# GamePad.net
KiCad netlist of a schematic drawn in EAGLE
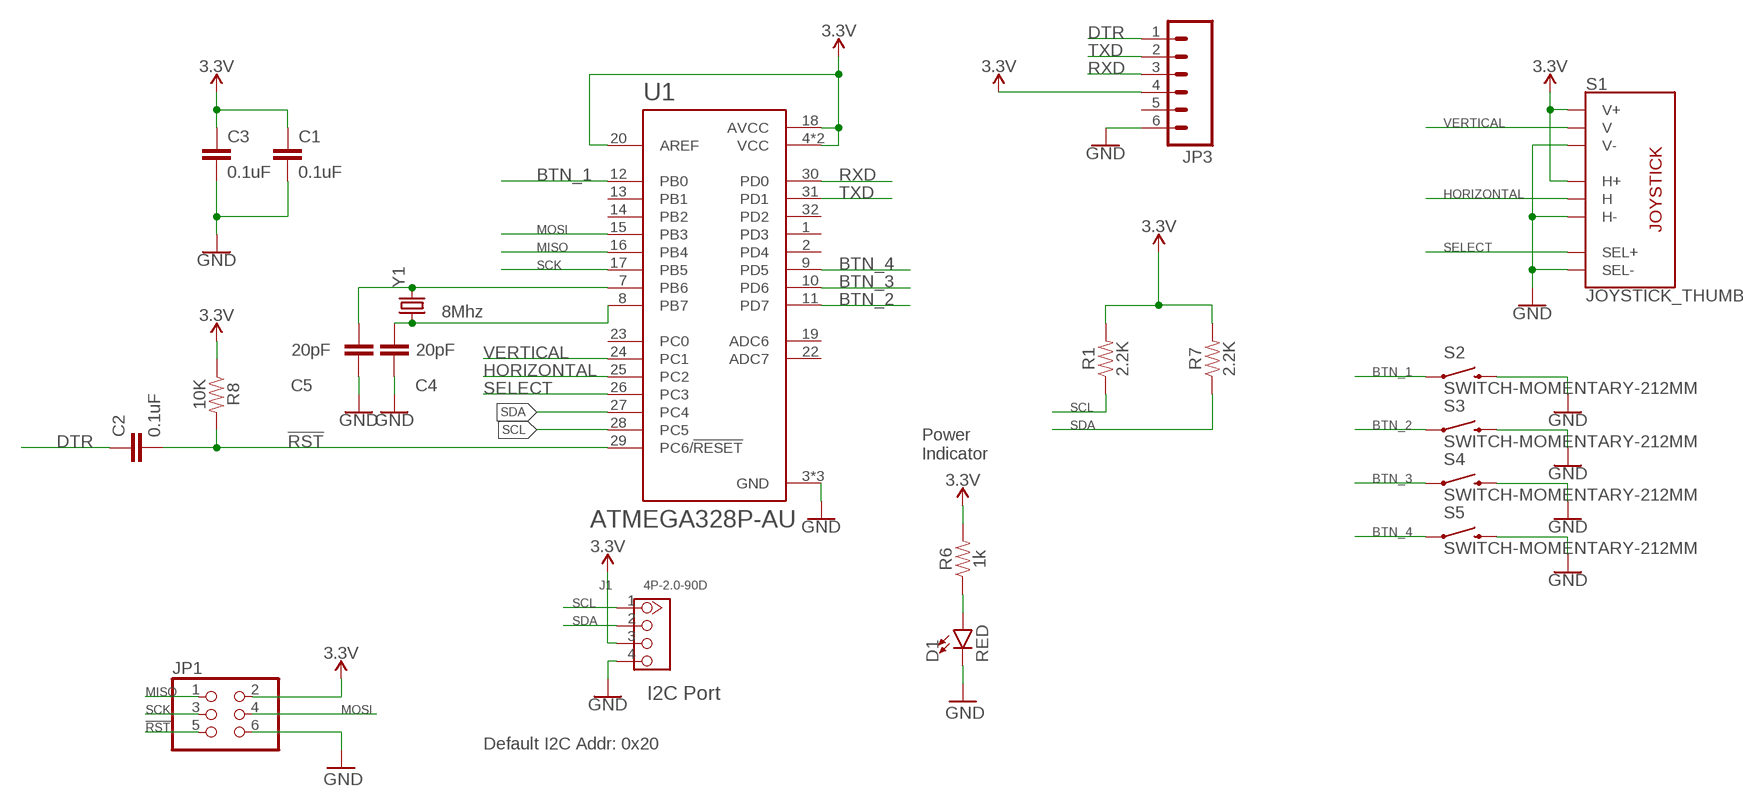
[diagram p0: schematic, sheet 1]

(export (version "E")
  (design (tool "Eeschema 10.0.6"))
  (components
    (comp (ref "C1")
      (value "0.1uF")
      (footprint "eagle-import:0603-CAP")
      (libsource (lib "eagle-import") (part "CAP0603-CAP"))
    )
    (comp (ref "C2")
      (value "0.1uF")
      (footprint "eagle-import:0603-CAP")
      (libsource (lib "eagle-import") (part "CAP0603-CAP"))
    )
    (comp (ref "C3")
      (value "0.1uF")
      (footprint "eagle-import:0603-CAP")
      (libsource (lib "eagle-import") (part "CAP0603-CAP"))
    )
    (comp (ref "C4")
      (value "20pF")
      (footprint "eagle-import:0603-CAP")
      (libsource (lib "eagle-import") (part "CAP0603-CAP"))
    )
    (comp (ref "C5")
      (value "20pF")
      (footprint "eagle-import:0603-CAP")
      (libsource (lib "eagle-import") (part "CAP0603-CAP"))
    )
    (comp (ref "D1")
      (value "RED")
      (footprint "eagle-import:LED-0603")
      (libsource (lib "eagle-import") (part "LED-RED0603"))
    )
    (comp (ref "J1")
      (value "4P-2.0-90D")
      (footprint "eagle-import:HW4-2.0-90D")
      (libsource (lib "eagle-import") (part "GROVE-CONNECTOR-DIP-90D(4P-2.0)"))
    )
    (comp (ref "JP1")
      (value "PINHD-2X3")
      (footprint "eagle-import:2X03")
      (libsource (lib "eagle-import") (part "PINHD-2X3"))
    )
    (comp (ref "JP3")
      (value "M06LOCK")
      (footprint "eagle-import:1X06_LOCK")
      (libsource (lib "eagle-import") (part "M06LOCK"))
    )
    (comp (ref "R1")
      (value "2.2K")
      (footprint "eagle-import:0603")
      (libsource (lib "eagle-import") (part "4.7KOHM-0603-1/10W-1%"))
    )
    (comp (ref "R6")
      (value "1k")
      (footprint "eagle-import:0603")
      (libsource (lib "eagle-import") (part "1KOHM-0603-1/10W-1%"))
    )
    (comp (ref "R7")
      (value "2.2K")
      (footprint "eagle-import:0603")
      (libsource (lib "eagle-import") (part "4.7KOHM-0603-1/10W-1%"))
    )
    (comp (ref "R8")
      (value "10K")
      (footprint "eagle-import:0603")
      (libsource (lib "eagle-import") (part "330OHM-0603-1/10W-1%"))
    )
    (comp (ref "S1")
      (value "JOYSTICK_THUMB")
      (footprint "eagle-import:JOYSTICK")
      (libsource (lib "eagle-import") (part "JOYSTICK_THUMB"))
    )
    (comp (ref "S2")
      (value "SWITCH-MOMENTARY-212MM")
      (footprint "eagle-import:TACTILE-PTH-12MM")
      (libsource (lib "eagle-import") (part "SWITCH-MOMENTARY-212MM"))
    )
    (comp (ref "S3")
      (value "SWITCH-MOMENTARY-212MM")
      (footprint "eagle-import:TACTILE-PTH-12MM")
      (libsource (lib "eagle-import") (part "SWITCH-MOMENTARY-212MM"))
    )
    (comp (ref "S4")
      (value "SWITCH-MOMENTARY-212MM")
      (footprint "eagle-import:TACTILE-PTH-12MM")
      (libsource (lib "eagle-import") (part "SWITCH-MOMENTARY-212MM"))
    )
    (comp (ref "S5")
      (value "SWITCH-MOMENTARY-212MM")
      (footprint "eagle-import:TACTILE-PTH-12MM")
      (libsource (lib "eagle-import") (part "SWITCH-MOMENTARY-212MM"))
    )
    (comp (ref "U1")
      (value "ATMEGA328P-AU")
      (footprint "eagle-import:QFP80P900X900X120-32N")
      (fields (field (name "MF") "Microchip"))
      (libsource (lib "eagle-import") (part "ATMEGA328P-AU"))
    )
    (comp (ref "Y1")
      (value "8Mhz")
      (footprint "eagle-import:HC49UP")
      (libsource (lib "eagle-import") (part "CRYSTALSMD"))
    )
  )
  (nets
    (net (code "1") (name "/BTN_1") (class "Default")
      (node (ref "S2") (pin "1") (pinfunction "1_1") (pintype "passive"))
      (node (ref "U1") (pin "12") (pinfunction "PB0_12") (pintype "bidirectional"))
    )
    (net (code "2") (name "/BTN_2") (class "Default")
      (node (ref "S3") (pin "1") (pinfunction "1_1") (pintype "passive"))
      (node (ref "U1") (pin "11") (pinfunction "PD7_11") (pintype "bidirectional"))
    )
    (net (code "3") (name "/BTN_3") (class "Default")
      (node (ref "S4") (pin "1") (pinfunction "1_1") (pintype "passive"))
      (node (ref "U1") (pin "10") (pinfunction "PD6_10") (pintype "bidirectional"))
    )
    (net (code "4") (name "/BTN_4") (class "Default")
      (node (ref "S5") (pin "1") (pinfunction "1_1") (pintype "passive"))
      (node (ref "U1") (pin "9") (pinfunction "PD5_9") (pintype "bidirectional"))
    )
    (net (code "5") (name "/DTR") (class "Default")
      (node (ref "C2") (pin "1") (pinfunction "1_1") (pintype "passive"))
      (node (ref "JP3") (pin "1") (pinfunction "1_1") (pintype "passive"))
    )
    (net (code "6") (name "/HORIZONTAL") (class "Default")
      (node (ref "S1") (pin "H2") (pinfunction "H_H2") (pintype "bidirectional"))
      (node (ref "U1") (pin "25") (pinfunction "PC2_25") (pintype "bidirectional"))
    )
    (net (code "7") (name "/MISO") (class "Default")
      (node (ref "JP1") (pin "1") (pinfunction "1_1") (pintype "passive"))
      (node (ref "U1") (pin "16") (pinfunction "PB4_16") (pintype "bidirectional"))
    )
    (net (code "8") (name "/MOSI") (class "Default")
      (node (ref "JP1") (pin "4") (pinfunction "4_4") (pintype "passive"))
      (node (ref "U1") (pin "15") (pinfunction "PB3_15") (pintype "bidirectional"))
    )
    (net (code "9") (name "/RXD") (class "Default")
      (node (ref "JP3") (pin "3") (pinfunction "3_3") (pintype "passive"))
      (node (ref "U1") (pin "30") (pinfunction "PD0_30") (pintype "bidirectional"))
    )
    (net (code "10") (name "/SCK") (class "Default")
      (node (ref "JP1") (pin "3") (pinfunction "3_3") (pintype "passive"))
      (node (ref "U1") (pin "17") (pinfunction "PB5_17") (pintype "bidirectional"))
    )
    (net (code "11") (name "/SELECT") (class "Default")
      (node (ref "S1") (pin "B1A") (pinfunction "SEL+_B1A") (pintype "bidirectional"))
      (node (ref "U1") (pin "26") (pinfunction "PC3_26") (pintype "bidirectional"))
    )
    (net (code "12") (name "/TXD") (class "Default")
      (node (ref "JP3") (pin "2") (pinfunction "2_2") (pintype "passive"))
      (node (ref "U1") (pin "31") (pinfunction "PD1_31") (pintype "bidirectional"))
    )
    (net (code "13") (name "/VERTICAL") (class "Default")
      (node (ref "S1") (pin "V2") (pinfunction "V_V2") (pintype "bidirectional"))
      (node (ref "U1") (pin "24") (pinfunction "PC1_24") (pintype "bidirectional"))
    )
    (net (code "14") (name "/~{RST}") (class "Default")
      (node (ref "C2") (pin "2") (pinfunction "2_2") (pintype "passive"))
      (node (ref "JP1") (pin "5") (pinfunction "5_5") (pintype "passive"))
      (node (ref "R8") (pin "2") (pinfunction "2_2") (pintype "passive"))
      (node (ref "U1") (pin "29") (pinfunction "PC6/~{RESET}_29") (pintype "bidirectional"))
    )
    (net (code "15") (name "3.3V") (class "Default")
      (node (ref "C1") (pin "1") (pinfunction "1_1") (pintype "passive"))
      (node (ref "C3") (pin "1") (pinfunction "1_1") (pintype "passive"))
      (node (ref "J1") (pin "3") (pinfunction "3_3") (pintype "bidirectional"))
      (node (ref "JP1") (pin "2") (pinfunction "2_2") (pintype "passive"))
      (node (ref "JP3") (pin "4") (pinfunction "4_4") (pintype "passive"))
      (node (ref "R1") (pin "2") (pinfunction "2_2") (pintype "passive"))
      (node (ref "R6") (pin "2") (pinfunction "2_2") (pintype "passive"))
      (node (ref "R7") (pin "2") (pinfunction "2_2") (pintype "passive"))
      (node (ref "R8") (pin "1") (pinfunction "1_1") (pintype "passive"))
      (node (ref "S1") (pin "H1") (pinfunction "H+_H1") (pintype "bidirectional"))
      (node (ref "S1") (pin "V1") (pinfunction "V+_V1") (pintype "bidirectional"))
      (node (ref "U1") (pin "18") (pinfunction "AVCC_18") (pintype "power_in"))
      (node (ref "U1") (pin "20") (pinfunction "AREF_20") (pintype "input"))
      (node (ref "U1") (pin "4") (pinfunction "VCC_4") (pintype "power_in"))
      (node (ref "U1") (pin "6") (pinfunction "VCC_6") (pintype "power_in"))
    )
    (net (code "16") (name "GND") (class "Default")
      (node (ref "C1") (pin "2") (pinfunction "2_2") (pintype "passive"))
      (node (ref "C3") (pin "2") (pinfunction "2_2") (pintype "passive"))
      (node (ref "C4") (pin "1") (pinfunction "1_1") (pintype "passive"))
      (node (ref "C5") (pin "1") (pinfunction "1_1") (pintype "passive"))
      (node (ref "D1") (pin "C") (pinfunction "C_C") (pintype "passive"))
      (node (ref "J1") (pin "4") (pinfunction "4_4") (pintype "bidirectional"))
      (node (ref "JP1") (pin "6") (pinfunction "6_6") (pintype "passive"))
      (node (ref "JP3") (pin "6") (pinfunction "6_6") (pintype "passive"))
      (node (ref "S1") (pin "B2A") (pinfunction "SEL-_B2A") (pintype "bidirectional"))
      (node (ref "S1") (pin "H3") (pinfunction "H-_H3") (pintype "bidirectional"))
      (node (ref "S1") (pin "V3") (pinfunction "V-_V3") (pintype "bidirectional"))
      (node (ref "S2") (pin "3") (pinfunction "2_3") (pintype "passive"))
      (node (ref "S3") (pin "3") (pinfunction "2_3") (pintype "passive"))
      (node (ref "S4") (pin "3") (pinfunction "2_3") (pintype "passive"))
      (node (ref "S5") (pin "3") (pinfunction "2_3") (pintype "passive"))
      (node (ref "U1") (pin "21") (pinfunction "GND_21") (pintype "power_in"))
      (node (ref "U1") (pin "3") (pinfunction "GND_3") (pintype "power_in"))
      (node (ref "U1") (pin "5") (pinfunction "GND_5") (pintype "power_in"))
    )
    (net (code "17") (name "Net-(D1-PadA)") (class "Default")
      (node (ref "D1") (pin "A") (pinfunction "A_A") (pintype "passive"))
      (node (ref "R6") (pin "1") (pinfunction "1_1") (pintype "passive"))
    )
    (net (code "18") (name "Net-(U1-PB6)") (class "Default")
      (node (ref "C5") (pin "2") (pinfunction "2_2") (pintype "passive"))
      (node (ref "U1") (pin "7") (pinfunction "PB6_7") (pintype "bidirectional"))
      (node (ref "Y1") (pin "2") (pinfunction "2_2") (pintype "passive"))
    )
    (net (code "19") (name "Net-(U1-PB7)") (class "Default")
      (node (ref "C4") (pin "2") (pinfunction "2_2") (pintype "passive"))
      (node (ref "U1") (pin "8") (pinfunction "PB7_8") (pintype "bidirectional"))
      (node (ref "Y1") (pin "1") (pinfunction "1_1") (pintype "passive"))
    )
    (net (code "20") (name "SCL") (class "Default")
      (node (ref "J1") (pin "1") (pinfunction "1_1") (pintype "bidirectional"))
      (node (ref "R1") (pin "1") (pinfunction "1_1") (pintype "passive"))
      (node (ref "U1") (pin "28") (pinfunction "PC5_28") (pintype "bidirectional"))
    )
    (net (code "21") (name "SDA") (class "Default")
      (node (ref "J1") (pin "2") (pinfunction "2_2") (pintype "bidirectional"))
      (node (ref "R7") (pin "1") (pinfunction "1_1") (pintype "passive"))
      (node (ref "U1") (pin "27") (pinfunction "PC4_27") (pintype "bidirectional"))
    )
    (net (code "22") (name "unconnected-(JP3-Pad5)") (class "Default")
      (node (ref "JP3") (pin "5") (pinfunction "5_5") (pintype "passive"))
    )
    (net (code "23") (name "unconnected-(U1-ADC6-Pad19)") (class "Default")
      (node (ref "U1") (pin "19") (pinfunction "ADC6_19") (pintype "bidirectional"))
    )
    (net (code "24") (name "unconnected-(U1-ADC7-Pad22)") (class "Default")
      (node (ref "U1") (pin "22") (pinfunction "ADC7_22") (pintype "bidirectional"))
    )
    (net (code "25") (name "unconnected-(U1-PB1-Pad13)") (class "Default")
      (node (ref "U1") (pin "13") (pinfunction "PB1_13") (pintype "bidirectional"))
    )
    (net (code "26") (name "unconnected-(U1-PB2-Pad14)") (class "Default")
      (node (ref "U1") (pin "14") (pinfunction "PB2_14") (pintype "bidirectional"))
    )
    (net (code "27") (name "unconnected-(U1-PC0-Pad23)") (class "Default")
      (node (ref "U1") (pin "23") (pinfunction "PC0_23") (pintype "bidirectional"))
    )
    (net (code "28") (name "unconnected-(U1-PD2-Pad32)") (class "Default")
      (node (ref "U1") (pin "32") (pinfunction "PD2_32") (pintype "bidirectional"))
    )
    (net (code "29") (name "unconnected-(U1-PD3-Pad1)") (class "Default")
      (node (ref "U1") (pin "1") (pinfunction "PD3_1") (pintype "bidirectional"))
    )
    (net (code "30") (name "unconnected-(U1-PD4-Pad2)") (class "Default")
      (node (ref "U1") (pin "2") (pinfunction "PD4_2") (pintype "bidirectional"))
    )
  )
)
